# control-pedal.net
KiCad netlist of a schematic drawn in Altium Designer
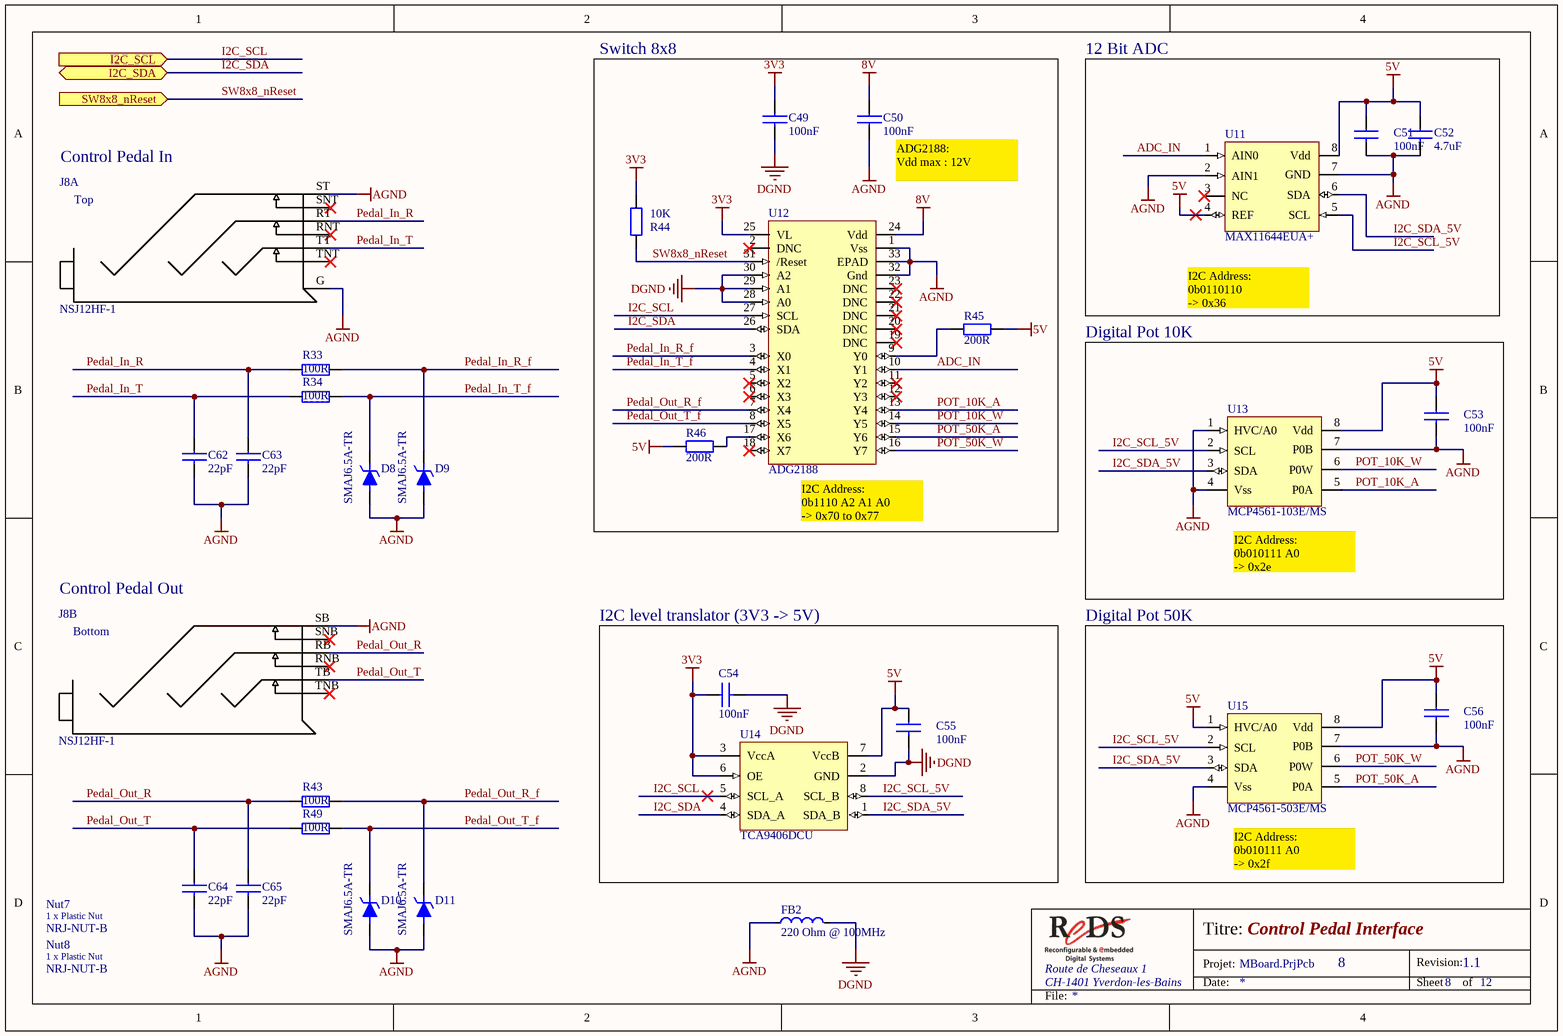
[diagram p0: control-pedal.SchDoc]

(export (version "E")
  (design (tool "Eeschema 10.0.6"))
  (components
    (comp (ref "C49")
      (value "100nF")
      (footprint "SM/C_0603")
      (description "Ceramic multi-layer")
      (fields (field (name "MANUFACTURER") "AVX") (field (name "VOLTAGE") "16V"))
      (libsource (lib "Database_heig-vd") (part "Cap"))
    )
    (comp (ref "C50")
      (value "100nF")
      (footprint "SM/C_0603")
      (description "Ceramic multi-layer")
      (fields (field (name "MANUFACTURER") "AVX") (field (name "VOLTAGE") "16V"))
      (libsource (lib "Database_heig-vd") (part "Cap"))
    )
    (comp (ref "C51")
      (value "100nF")
      (footprint "SM/C_0603")
      (description "Ceramic multi-layer")
      (fields (field (name "MANUFACTURER") "AVX") (field (name "VOLTAGE") "16V"))
      (libsource (lib "Database_heig-vd") (part "Cap"))
    )
    (comp (ref "C52")
      (value "4.7uF")
      (footprint "SM/C_0805")
      (description "Ceramic multi-layer")
      (fields (field (name "MANUFACTURER") "muRata") (field (name "VOLTAGE") "6.3V"))
      (libsource (lib "Database_heig-vd") (part "Cap"))
    )
    (comp (ref "C53")
      (value "100nF")
      (footprint "SM/C_0603")
      (description "Ceramic multi-layer")
      (fields (field (name "MANUFACTURER") "AVX") (field (name "VOLTAGE") "16V"))
      (libsource (lib "Database_heig-vd") (part "Cap"))
    )
    (comp (ref "C54")
      (value "100nF")
      (footprint "SM/C_0603")
      (description "Ceramic multi-layer")
      (fields (field (name "MANUFACTURER") "AVX") (field (name "VOLTAGE") "16V"))
      (libsource (lib "Database_heig-vd") (part "Cap"))
    )
    (comp (ref "C55")
      (value "100nF")
      (footprint "SM/C_0603")
      (description "Ceramic multi-layer")
      (fields (field (name "MANUFACTURER") "AVX") (field (name "VOLTAGE") "16V"))
      (libsource (lib "Database_heig-vd") (part "Cap"))
    )
    (comp (ref "C56")
      (value "100nF")
      (footprint "SM/C_0603")
      (description "Ceramic multi-layer")
      (fields (field (name "MANUFACTURER") "AVX") (field (name "VOLTAGE") "16V"))
      (libsource (lib "Database_heig-vd") (part "Cap"))
    )
    (comp (ref "C62")
      (value "22pF")
      (footprint "SM/C_0603")
      (description "Capacitor, ceramic")
      (fields (field (name "MANUFACTURER") "Kemet ") (field (name "VOLTAGE") "50V"))
      (libsource (lib "Database_heig-vd") (part "Cap"))
    )
    (comp (ref "C63")
      (value "22pF")
      (footprint "SM/C_0603")
      (description "Capacitor, ceramic")
      (fields (field (name "MANUFACTURER") "Kemet ") (field (name "VOLTAGE") "50V"))
      (libsource (lib "Database_heig-vd") (part "Cap"))
    )
    (comp (ref "C64")
      (value "22pF")
      (footprint "SM/C_0603")
      (description "Capacitor, ceramic")
      (fields (field (name "MANUFACTURER") "Kemet ") (field (name "VOLTAGE") "50V"))
      (libsource (lib "Database_heig-vd") (part "Cap"))
    )
    (comp (ref "C65")
      (value "22pF")
      (footprint "SM/C_0603")
      (description "Capacitor, ceramic")
      (fields (field (name "MANUFACTURER") "Kemet ") (field (name "VOLTAGE") "50V"))
      (libsource (lib "Database_heig-vd") (part "Cap"))
    )
    (comp (ref "D8")
      (value "SMAJ6.5A-TR")
      (footprint "SM/D_DO214-AC (SMA)")
      (description "Transil™ diode")
      (fields (field (name "MANUFACTURER") "STMicroelectronics"))
      (libsource (lib "Database_heig-vd") (part "Diode TVS Unidirectional/A1C2"))
    )
    (comp (ref "D9")
      (value "SMAJ6.5A-TR")
      (footprint "SM/D_DO214-AC (SMA)")
      (description "Transil™ diode")
      (fields (field (name "MANUFACTURER") "STMicroelectronics"))
      (libsource (lib "Database_heig-vd") (part "Diode TVS Unidirectional/A1C2"))
    )
    (comp (ref "D10")
      (value "SMAJ6.5A-TR")
      (footprint "SM/D_DO214-AC (SMA)")
      (description "Transil™ diode")
      (fields (field (name "MANUFACTURER") "STMicroelectronics"))
      (libsource (lib "Database_heig-vd") (part "Diode TVS Unidirectional/A1C2"))
    )
    (comp (ref "D11")
      (value "SMAJ6.5A-TR")
      (footprint "SM/D_DO214-AC (SMA)")
      (description "Transil™ diode")
      (fields (field (name "MANUFACTURER") "STMicroelectronics"))
      (libsource (lib "Database_heig-vd") (part "Diode TVS Unidirectional/A1C2"))
    )
    (comp (ref "FB2")
      (value "220 Ohm @ 100MHz")
      (footprint "SM/L_0805")
      (description "PERLE DE FERRITE 0805. 220 OHMS/100MHz")
      (fields (field (name "MANUFACTURER") "Murata") (field (name "TOLERANCE") "± 25%"))
      (libsource (lib "Database_heig-vd") (part "Ferrite"))
    )
    (comp (ref "J8")
      (value "NSJ12HF-1")
      (footprint "NSJ12HF-1")
      (description "Neutronik 2xJack 6.35 connector")
      (libsource (lib "MBoard") (part "Jack 6.35 NSJ12HF-1"))
    )
    (comp (ref "Nut7")
      (value "NRJ-NUT-B")
      (description "Plastic Nut to fasten 6.35 jack")
      (fields (field (name "MANUFACTURER") "Neutrik"))
      (libsource (lib "MBoard") (part "Jack 6.35 Plastic Nut"))
    )
    (comp (ref "Nut8")
      (value "NRJ-NUT-B")
      (description "Plastic Nut to fasten 6.35 jack")
      (fields (field (name "MANUFACTURER") "Neutrik"))
      (libsource (lib "MBoard") (part "Jack 6.35 Plastic Nut"))
    )
    (comp (ref "R33")
      (value "100R")
      (footprint "SM/R_0603")
      (description "Résistance 0603 63mW 1% 100R")
      (fields (field (name "MANUFACTURER") "Multicomp") (field (name "POWER") "63mW"))
      (libsource (lib "Database_heig-vd") (part "Res"))
    )
    (comp (ref "R34")
      (value "100R")
      (footprint "SM/R_0603")
      (description "Résistance 0603 63mW 1% 100R")
      (fields (field (name "MANUFACTURER") "Multicomp") (field (name "POWER") "63mW"))
      (libsource (lib "Database_heig-vd") (part "Res"))
    )
    (comp (ref "R43")
      (value "100R")
      (footprint "SM/R_0603")
      (description "Résistance 0603 63mW 1% 100R")
      (fields (field (name "MANUFACTURER") "Multicomp") (field (name "POWER") "63mW"))
      (libsource (lib "Database_heig-vd") (part "Res"))
    )
    (comp (ref "R44")
      (value "10K")
      (footprint "SM/R_0603")
      (description "Résistance 0603 63mW 1% 10K")
      (fields (field (name "MANUFACTURER") "Multicomp") (field (name "POWER") "63mW"))
      (libsource (lib "Database_heig-vd") (part "Res"))
    )
    (comp (ref "R45")
      (value "200R")
      (footprint "SM/R_0603")
      (description "Résistance 0603 63mW 1% 200R")
      (fields (field (name "MANUFACTURER") "Multicomp") (field (name "POWER") "63mW"))
      (libsource (lib "Database_heig-vd") (part "Res"))
    )
    (comp (ref "R46")
      (value "200R")
      (footprint "SM/R_0603")
      (description "Résistance 0603 63mW 1% 200R")
      (fields (field (name "MANUFACTURER") "Multicomp") (field (name "POWER") "63mW"))
      (libsource (lib "Database_heig-vd") (part "Res"))
    )
    (comp (ref "R49")
      (value "100R")
      (footprint "SM/R_0603")
      (description "Résistance 0603 63mW 1% 100R")
      (fields (field (name "MANUFACTURER") "Multicomp") (field (name "POWER") "63mW"))
      (libsource (lib "Database_heig-vd") (part "Res"))
    )
    (comp (ref "U11")
      (value "MAX11644EUA+")
      (footprint "uMAX-8")
      (description "ADC 12Bit I2C")
      (libsource (lib "MBoard") (part "MAX11644"))
    )
    (comp (ref "U12")
      (value "ADG2188")
      (footprint "VFQFN-32_(32-Lead LFCSP_VQ)")
      (description "Switch 8x8")
      (libsource (lib "MBoard") (part "ADG2188"))
    )
    (comp (ref "U13")
      (value "MCP4561-103E/MS")
      (footprint "MSOP-8")
      (description "I2C Digital pot 10K")
      (libsource (lib "MBoard") (part "MCP4561-103E/MS"))
    )
    (comp (ref "U14")
      (value "TCA9406DCU")
      (footprint "VSSOP-8")
      (description "I2C Voltage level translator")
      (libsource (lib "MBoard") (part "TCA9406"))
    )
    (comp (ref "U15")
      (value "MCP4561-503E/MS")
      (footprint "MSOP-8")
      (description "I2C Digital pot 50K")
      (libsource (lib "MBoard") (part "MCP4561-503E/MS"))
    )
  )
  (nets
    (net (code "1") (name "/ADC_IN") (class "Default")
      (node (ref "U11") (pin "1") (pinfunction "AIN0_1") (pintype "input"))
      (node (ref "U12") (pin "10") (pinfunction "Y1_10") (pintype "bidirectional"))
    )
    (net (code "2") (name "/I2C_SCL") (class "Default")
      (node (ref "U12") (pin "27") (pinfunction "SCL_27") (pintype "input"))
      (node (ref "U14") (pin "5") (pinfunction "SCL_A_5") (pintype "bidirectional"))
    )
    (net (code "3") (name "/I2C_SCL_5V") (class "Default")
      (node (ref "U11") (pin "5") (pinfunction "SCL_5") (pintype "input"))
      (node (ref "U13") (pin "2") (pinfunction "SCL_2") (pintype "input"))
      (node (ref "U14") (pin "8") (pinfunction "SCL_B_8") (pintype "bidirectional"))
      (node (ref "U15") (pin "2") (pinfunction "SCL_2") (pintype "input"))
    )
    (net (code "4") (name "/I2C_SDA") (class "Default")
      (node (ref "U12") (pin "26") (pinfunction "SDA_26") (pintype "bidirectional"))
      (node (ref "U14") (pin "4") (pinfunction "SDA_A_4") (pintype "bidirectional"))
    )
    (net (code "5") (name "/I2C_SDA_5V") (class "Default")
      (node (ref "U11") (pin "6") (pinfunction "SDA_6") (pintype "bidirectional"))
      (node (ref "U13") (pin "3") (pinfunction "SDA_3") (pintype "bidirectional"))
      (node (ref "U14") (pin "1") (pinfunction "SDA_B_1") (pintype "bidirectional"))
      (node (ref "U15") (pin "3") (pinfunction "SDA_3") (pintype "bidirectional"))
    )
    (net (code "6") (name "/POT_10K_A") (class "Default")
      (node (ref "U12") (pin "13") (pinfunction "Y4_13") (pintype "bidirectional"))
      (node (ref "U13") (pin "5") (pinfunction "P0A_5") (pintype "passive"))
    )
    (net (code "7") (name "/POT_10K_W") (class "Default")
      (node (ref "U12") (pin "14") (pinfunction "Y5_14") (pintype "bidirectional"))
      (node (ref "U13") (pin "6") (pinfunction "P0W_6") (pintype "passive"))
    )
    (net (code "8") (name "/POT_50K_A") (class "Default")
      (node (ref "U12") (pin "15") (pinfunction "Y6_15") (pintype "bidirectional"))
      (node (ref "U15") (pin "5") (pinfunction "P0A_5") (pintype "passive"))
    )
    (net (code "9") (name "/POT_50K_W") (class "Default")
      (node (ref "U12") (pin "16") (pinfunction "Y7_16") (pintype "bidirectional"))
      (node (ref "U15") (pin "6") (pinfunction "P0W_6") (pintype "passive"))
    )
    (net (code "10") (name "/Pedal_In_R") (class "Default")
      (node (ref "C63") (pin "1") (pinfunction "1_1") (pintype "passive"))
      (node (ref "J8") (pin "RT") (pintype "passive"))
      (node (ref "R33") (pin "1") (pinfunction "1_1") (pintype "passive"))
    )
    (net (code "11") (name "/Pedal_In_R_f") (class "Default")
      (node (ref "D9") (pin "2") (pinfunction "C_2") (pintype "passive"))
      (node (ref "R33") (pin "2") (pinfunction "2_2") (pintype "passive"))
      (node (ref "U12") (pin "3") (pinfunction "X0_3") (pintype "bidirectional"))
    )
    (net (code "12") (name "/Pedal_In_T") (class "Default")
      (node (ref "C62") (pin "1") (pinfunction "1_1") (pintype "passive"))
      (node (ref "J8") (pin "TT") (pintype "passive"))
      (node (ref "R34") (pin "1") (pinfunction "1_1") (pintype "passive"))
    )
    (net (code "13") (name "/Pedal_In_T_f") (class "Default")
      (node (ref "D8") (pin "2") (pinfunction "C_2") (pintype "passive"))
      (node (ref "R34") (pin "2") (pinfunction "2_2") (pintype "passive"))
      (node (ref "U12") (pin "4") (pinfunction "X1_4") (pintype "bidirectional"))
    )
    (net (code "14") (name "/Pedal_Out_R") (class "Default")
      (node (ref "C65") (pin "1") (pinfunction "1_1") (pintype "passive"))
      (node (ref "J8") (pin "RB") (pintype "passive"))
      (node (ref "R43") (pin "1") (pinfunction "1_1") (pintype "passive"))
    )
    (net (code "15") (name "/Pedal_Out_R_f") (class "Default")
      (node (ref "D11") (pin "2") (pinfunction "C_2") (pintype "passive"))
      (node (ref "R43") (pin "2") (pinfunction "2_2") (pintype "passive"))
      (node (ref "U12") (pin "7") (pinfunction "X4_7") (pintype "bidirectional"))
    )
    (net (code "16") (name "/Pedal_Out_T") (class "Default")
      (node (ref "C64") (pin "1") (pinfunction "1_1") (pintype "passive"))
      (node (ref "J8") (pin "TB") (pintype "passive"))
      (node (ref "R49") (pin "1") (pinfunction "1_1") (pintype "passive"))
    )
    (net (code "17") (name "/Pedal_Out_T_f") (class "Default")
      (node (ref "D10") (pin "2") (pinfunction "C_2") (pintype "passive"))
      (node (ref "R49") (pin "2") (pinfunction "2_2") (pintype "passive"))
      (node (ref "U12") (pin "8") (pinfunction "X5_8") (pintype "bidirectional"))
    )
    (net (code "18") (name "/SW8x8_nReset") (class "Default")
      (node (ref "R44") (pin "2") (pinfunction "2_2") (pintype "passive"))
      (node (ref "U12") (pin "31") (pinfunction "/Reset_31") (pintype "input"))
    )
    (net (code "19") (name "3V3") (class "Default")
      (node (ref "C49") (pin "1") (pinfunction "1_1") (pintype "passive"))
      (node (ref "C54") (pin "1") (pinfunction "1_1") (pintype "passive"))
      (node (ref "R44") (pin "1") (pinfunction "1_1") (pintype "passive"))
      (node (ref "U12") (pin "25") (pinfunction "VL_25") (pintype "power_in"))
      (node (ref "U14") (pin "3") (pinfunction "VccA_3") (pintype "power_in"))
      (node (ref "U14") (pin "6") (pinfunction "OE_6") (pintype "input"))
    )
    (net (code "20") (name "5V") (class "Default")
      (node (ref "C51") (pin "1") (pinfunction "1_1") (pintype "passive"))
      (node (ref "C52") (pin "1") (pinfunction "1_1") (pintype "passive"))
      (node (ref "C53") (pin "1") (pinfunction "1_1") (pintype "passive"))
      (node (ref "C55") (pin "1") (pinfunction "1_1") (pintype "passive"))
      (node (ref "C56") (pin "1") (pinfunction "1_1") (pintype "passive"))
      (node (ref "R45") (pin "2") (pinfunction "2_2") (pintype "passive"))
      (node (ref "R46") (pin "1") (pinfunction "1_1") (pintype "passive"))
      (node (ref "U11") (pin "4") (pinfunction "REF_4") (pintype "bidirectional"))
      (node (ref "U11") (pin "8") (pinfunction "Vdd_8") (pintype "power_in"))
      (node (ref "U13") (pin "8") (pinfunction "Vdd_8") (pintype "power_in"))
      (node (ref "U14") (pin "7") (pinfunction "VccB_7") (pintype "power_in"))
      (node (ref "U15") (pin "1") (pinfunction "HVC/A0_1") (pintype "input"))
      (node (ref "U15") (pin "8") (pinfunction "Vdd_8") (pintype "power_in"))
    )
    (net (code "21") (name "8V") (class "Default")
      (node (ref "C50") (pin "1") (pinfunction "1_1") (pintype "passive"))
      (node (ref "U12") (pin "24") (pinfunction "Vdd_24") (pintype "power_in"))
    )
    (net (code "22") (name "AGND") (class "Default")
      (node (ref "C50") (pin "2") (pinfunction "2_2") (pintype "passive"))
      (node (ref "C51") (pin "2") (pinfunction "2_2") (pintype "passive"))
      (node (ref "C52") (pin "2") (pinfunction "2_2") (pintype "passive"))
      (node (ref "C53") (pin "2") (pinfunction "2_2") (pintype "passive"))
      (node (ref "C56") (pin "2") (pinfunction "2_2") (pintype "passive"))
      (node (ref "C62") (pin "2") (pinfunction "2_2") (pintype "passive"))
      (node (ref "C63") (pin "2") (pinfunction "2_2") (pintype "passive"))
      (node (ref "C64") (pin "2") (pinfunction "2_2") (pintype "passive"))
      (node (ref "C65") (pin "2") (pinfunction "2_2") (pintype "passive"))
      (node (ref "D10") (pin "1") (pinfunction "A_1") (pintype "passive"))
      (node (ref "D11") (pin "1") (pinfunction "A_1") (pintype "passive"))
      (node (ref "D8") (pin "1") (pinfunction "A_1") (pintype "passive"))
      (node (ref "D9") (pin "1") (pinfunction "A_1") (pintype "passive"))
      (node (ref "FB2") (pin "1") (pinfunction "1_1") (pintype "passive"))
      (node (ref "J8") (pin "G") (pinfunction "G_G") (pintype "passive"))
      (node (ref "J8") (pin "SB") (pintype "passive"))
      (node (ref "J8") (pin "ST") (pintype "passive"))
      (node (ref "U11") (pin "2") (pinfunction "AIN1_2") (pintype "input"))
      (node (ref "U11") (pin "7") (pinfunction "GND_7") (pintype "power_in"))
      (node (ref "U12") (pin "1") (pinfunction "Vss_1") (pintype "power_in"))
      (node (ref "U12") (pin "32") (pinfunction "Gnd_32") (pintype "power_in"))
      (node (ref "U12") (pin "33") (pinfunction "EPAD_33") (pintype "power_in"))
      (node (ref "U13") (pin "1") (pinfunction "HVC/A0_1") (pintype "input"))
      (node (ref "U13") (pin "4") (pinfunction "Vss_4") (pintype "power_in"))
      (node (ref "U13") (pin "7") (pinfunction "P0B_7") (pintype "passive"))
      (node (ref "U15") (pin "4") (pinfunction "Vss_4") (pintype "power_in"))
      (node (ref "U15") (pin "7") (pinfunction "P0B_7") (pintype "passive"))
    )
    (net (code "23") (name "DGND") (class "Default")
      (node (ref "C49") (pin "2") (pinfunction "2_2") (pintype "passive"))
      (node (ref "C54") (pin "2") (pinfunction "2_2") (pintype "passive"))
      (node (ref "C55") (pin "2") (pinfunction "2_2") (pintype "passive"))
      (node (ref "FB2") (pin "2") (pinfunction "2_2") (pintype "passive"))
      (node (ref "U12") (pin "28") (pinfunction "A0_28") (pintype "input"))
      (node (ref "U12") (pin "29") (pinfunction "A1_29") (pintype "input"))
      (node (ref "U12") (pin "30") (pinfunction "A2_30") (pintype "input"))
      (node (ref "U14") (pin "2") (pinfunction "GND_2") (pintype "power_in"))
    )
    (net (code "24") (name "Net-(U12-X6)") (class "Default")
      (node (ref "R46") (pin "2") (pinfunction "2_2") (pintype "passive"))
      (node (ref "U12") (pin "17") (pinfunction "X6_17") (pintype "bidirectional"))
    )
    (net (code "25") (name "Net-(U12-Y0)") (class "Default")
      (node (ref "R45") (pin "1") (pinfunction "1_1") (pintype "passive"))
      (node (ref "U12") (pin "9") (pinfunction "Y0_9") (pintype "bidirectional"))
    )
    (net (code "26") (name "unconnected-(J8-PadRNB)") (class "Default")
      (node (ref "J8") (pin "RNB") (pintype "passive+no_connect"))
    )
    (net (code "27") (name "unconnected-(J8-PadRNT)") (class "Default")
      (node (ref "J8") (pin "RNT") (pintype "passive+no_connect"))
    )
    (net (code "28") (name "unconnected-(J8-PadSNB)") (class "Default")
      (node (ref "J8") (pin "SNB") (pintype "passive+no_connect"))
    )
    (net (code "29") (name "unconnected-(J8-PadSNT)") (class "Default")
      (node (ref "J8") (pin "SNT") (pintype "passive+no_connect"))
    )
    (net (code "30") (name "unconnected-(J8-PadTNB)") (class "Default")
      (node (ref "J8") (pin "TNB") (pintype "passive+no_connect"))
    )
    (net (code "31") (name "unconnected-(J8-PadTNT)") (class "Default")
      (node (ref "J8") (pin "TNT") (pintype "passive+no_connect"))
    )
    (net (code "32") (name "unconnected-(U11-NC-Pad3)") (class "Default")
      (node (ref "U11") (pin "3") (pinfunction "NC_3") (pintype "passive+no_connect"))
    )
    (net (code "33") (name "unconnected-(U12-DNC-Pad2)") (class "Default")
      (node (ref "U12") (pin "2") (pinfunction "DNC_2") (pintype "passive+no_connect"))
    )
    (net (code "34") (name "unconnected-(U12-DNC-Pad19)") (class "Default")
      (node (ref "U12") (pin "19") (pinfunction "DNC_19") (pintype "passive+no_connect"))
    )
    (net (code "35") (name "unconnected-(U12-DNC-Pad20)") (class "Default")
      (node (ref "U12") (pin "20") (pinfunction "DNC_20") (pintype "passive+no_connect"))
    )
    (net (code "36") (name "unconnected-(U12-DNC-Pad21)") (class "Default")
      (node (ref "U12") (pin "21") (pinfunction "DNC_21") (pintype "passive+no_connect"))
    )
    (net (code "37") (name "unconnected-(U12-DNC-Pad22)") (class "Default")
      (node (ref "U12") (pin "22") (pinfunction "DNC_22") (pintype "passive+no_connect"))
    )
    (net (code "38") (name "unconnected-(U12-DNC-Pad23)") (class "Default")
      (node (ref "U12") (pin "23") (pinfunction "DNC_23") (pintype "passive+no_connect"))
    )
    (net (code "39") (name "unconnected-(U12-X2-Pad5)") (class "Default")
      (node (ref "U12") (pin "5") (pinfunction "X2_5") (pintype "bidirectional+no_connect"))
    )
    (net (code "40") (name "unconnected-(U12-X3-Pad6)") (class "Default")
      (node (ref "U12") (pin "6") (pinfunction "X3_6") (pintype "bidirectional+no_connect"))
    )
    (net (code "41") (name "unconnected-(U12-X7-Pad18)") (class "Default")
      (node (ref "U12") (pin "18") (pinfunction "X7_18") (pintype "bidirectional+no_connect"))
    )
    (net (code "42") (name "unconnected-(U12-Y2-Pad11)") (class "Default")
      (node (ref "U12") (pin "11") (pinfunction "Y2_11") (pintype "bidirectional+no_connect"))
    )
    (net (code "43") (name "unconnected-(U12-Y3-Pad12)") (class "Default")
      (node (ref "U12") (pin "12") (pinfunction "Y3_12") (pintype "bidirectional+no_connect"))
    )
  )
)
